# BEEP.net
KiCad netlist of a schematic drawn in Altium Designer
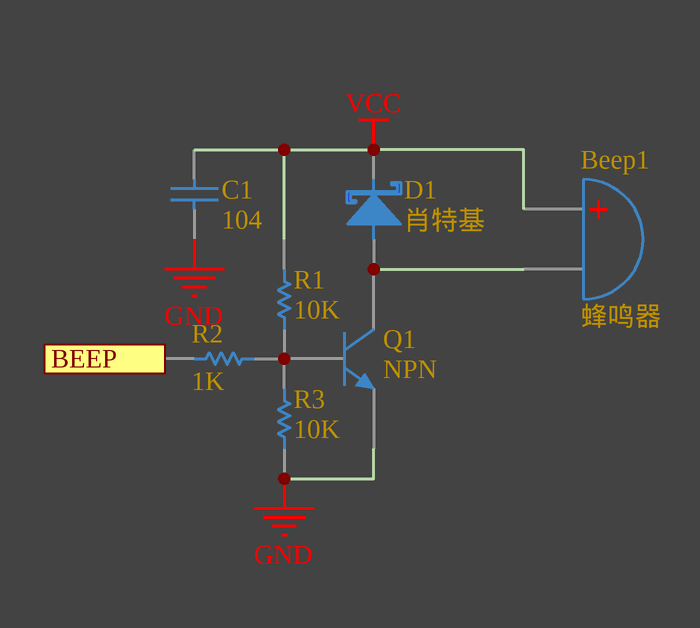
[diagram p0: BEEP.SchDoc]

(export (version "E")
  (design (tool "Eeschema 10.0.6"))
  (components
    (comp (ref "Beep1") (value "蜂鸣器") (footprint "Beep-5.0*5.0") (libsource (lib "iMag") (part "蜂鸣器")))
    (comp (ref "C1")
      (value "104")
      (footprint "C0402")
      (description "Capacitor")
      (fields (field (name "PUBLISHER") "Altium Limited"))
      (libsource (lib "iMag") (part "电容"))
    )
    (comp (ref "D1")
      (value "肖特基")
      (footprint "SOD-123F")
      (description "Schottky Diode")
      (libsource (lib "iMag") (part "肖特基"))
    )
    (comp (ref "Q1")
      (value "NPN")
      (footprint "SOT-23")
      (description "NPN Bipolar Transistor")
      (fields (field (name "PUBLISHER") "Altium Limited"))
      (libsource (lib "iMag") (part "NPN"))
    )
    (comp (ref "R1")
      (value "10K")
      (footprint "R0402")
      (description "Resistor")
      (fields (field (name "PUBLISHER") "Altium Limited"))
      (libsource (lib "iMag") (part "电阻"))
    )
    (comp (ref "R2")
      (value "1K")
      (footprint "R0402")
      (description "Resistor")
      (fields (field (name "PUBLISHER") "Altium Limited"))
      (libsource (lib "iMag") (part "电阻"))
    )
    (comp (ref "R3")
      (value "10K")
      (footprint "R0402")
      (description "Resistor")
      (fields (field (name "PUBLISHER") "Altium Limited"))
      (libsource (lib "iMag") (part "电阻"))
    )
  )
  (nets
    (net (code "1") (name "/BEEP") (class "Default")
      (node (ref "R2") (pin "2") (pinfunction "2_2") (pintype "passive"))
    )
    (net (code "2") (name "GND") (class "Default")
      (node (ref "C1") (pin "1") (pinfunction "1_1") (pintype "passive"))
      (node (ref "Q1") (pin "2") (pinfunction "E_2") (pintype "passive"))
      (node (ref "R3") (pin "1") (pinfunction "1_1") (pintype "passive"))
    )
    (net (code "3") (name "Net-(Beep1-B)") (class "Default")
      (node (ref "Beep1") (pin "2") (pinfunction "B_2") (pintype "passive"))
      (node (ref "D1") (pin "1") (pinfunction "A_1") (pintype "passive"))
      (node (ref "Q1") (pin "3") (pinfunction "C_3") (pintype "passive"))
    )
    (net (code "4") (name "Net-(Q1-B)") (class "Default")
      (node (ref "Q1") (pin "1") (pinfunction "B_1") (pintype "passive"))
      (node (ref "R1") (pin "1") (pinfunction "1_1") (pintype "passive"))
      (node (ref "R2") (pin "1") (pinfunction "1_1") (pintype "passive"))
      (node (ref "R3") (pin "2") (pinfunction "2_2") (pintype "passive"))
    )
    (net (code "5") (name "VCC") (class "Default")
      (node (ref "Beep1") (pin "1") (pinfunction "A_1") (pintype "passive"))
      (node (ref "C1") (pin "2") (pinfunction "2_2") (pintype "passive"))
      (node (ref "D1") (pin "2") (pinfunction "K_2") (pintype "passive"))
      (node (ref "R1") (pin "2") (pinfunction "2_2") (pintype "passive"))
    )
  )
)
